# doorEntryIoT.net
KiCad netlist of a schematic drawn in EAGLE
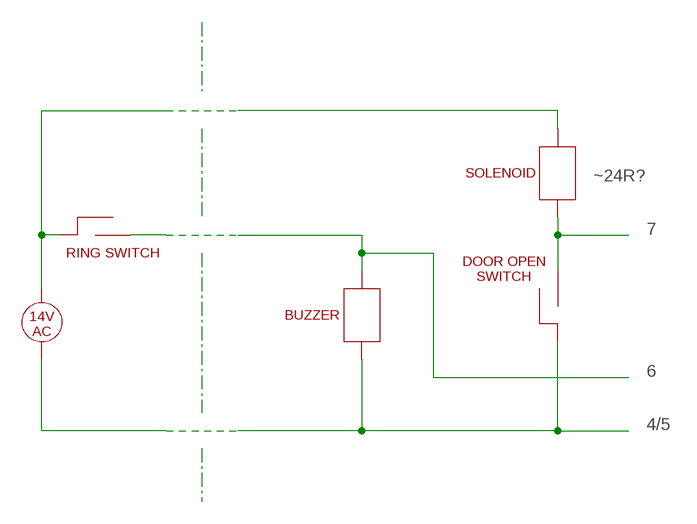
[diagram p0: schematic, sheet 1, part 1 of 2]
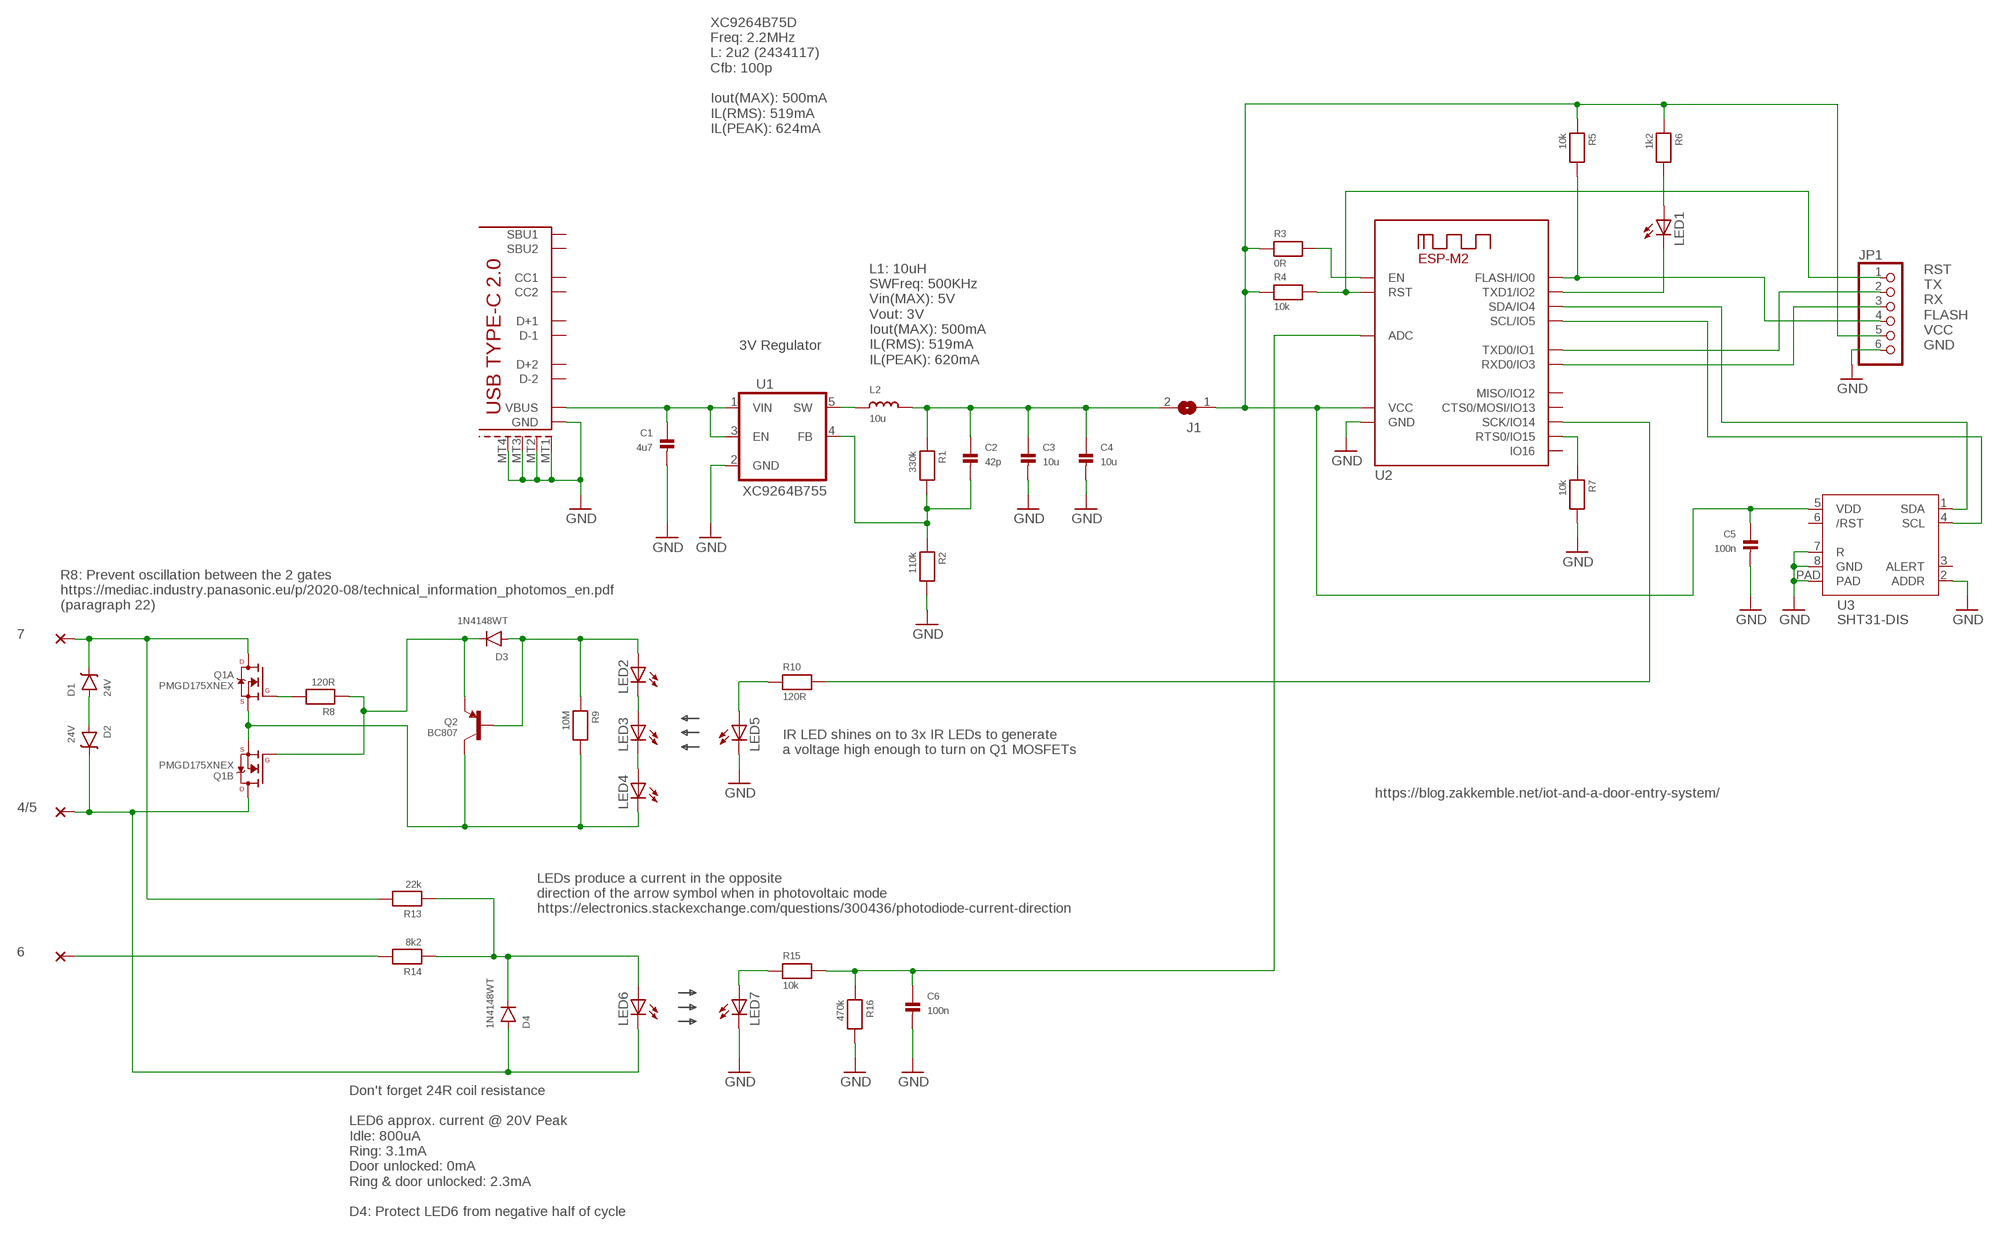
[diagram p1: schematic, sheet 1, part 2 of 2]

(export (version "E")
  (design (tool "Eeschema 10.0.6"))
  (components
    (comp (ref "C1")
      (value "4u7")
      (footprint "eagle-import:0805_NO_OUTLINE")
      (libsource (lib "eagle-import") (part "CAP_CERAMIC0805"))
    )
    (comp (ref "C2")
      (value "42p")
      (footprint "eagle-import:0402_XSMALL")
      (libsource (lib "eagle-import") (part "CAP_CERAMIC0402_XSMALL"))
    )
    (comp (ref "C3")
      (value "10u")
      (footprint "eagle-import:1206")
      (libsource (lib "eagle-import") (part "CAP_CERAMIC1206"))
    )
    (comp (ref "C4")
      (value "10u")
      (footprint "eagle-import:1206")
      (libsource (lib "eagle-import") (part "CAP_CERAMIC1206"))
    )
    (comp (ref "C5")
      (value "100n")
      (footprint "eagle-import:0402_XSMALL")
      (libsource (lib "eagle-import") (part "CAP_CERAMIC0402_XSMALL"))
    )
    (comp (ref "C6")
      (value "100n")
      (footprint "eagle-import:0402_XSMALL")
      (libsource (lib "eagle-import") (part "CAP_CERAMIC0402_XSMALL"))
    )
    (comp (ref "D1")
      (value "24V")
      (footprint "eagle-import:SMA")
      (libsource (lib "eagle-import") (part "DIODE-ZENERSMA"))
    )
    (comp (ref "D2")
      (value "24V")
      (footprint "eagle-import:SMA")
      (libsource (lib "eagle-import") (part "DIODE-ZENERSMA"))
    )
    (comp (ref "D3")
      (value "1N4148WT")
      (footprint "eagle-import:SOD-523_SM")
      (libsource (lib "eagle-import") (part "DIODESOD-523_SM"))
    )
    (comp (ref "D4")
      (value "1N4148WT")
      (footprint "eagle-import:SOD-523_SM")
      (libsource (lib "eagle-import") (part "DIODESOD-523_SM"))
    )
    (comp (ref "J1")
      (value "JUMPERSMALL")
      (footprint "eagle-import:JUMPER_SMALL")
      (libsource (lib "eagle-import") (part "JUMPERSMALL"))
    )
    (comp (ref "JP1")
      (value "PINHD-1X6")
      (footprint "eagle-import:1X06")
      (libsource (lib "eagle-import") (part "PINHD-1X6"))
    )
    (comp (ref "L2")
      (value "10u")
      (footprint "eagle-import:1210K")
      (libsource (lib "eagle-import") (part "INDUCTOR1210K"))
    )
    (comp (ref "LED1")
      (value "LED0402_XSMALL")
      (footprint "eagle-import:0402_DIODE_XSMALL")
      (libsource (lib "eagle-import") (part "LED0402_XSMALL"))
    )
    (comp (ref "LED2")
      (value "LEDSIDEVIEW")
      (footprint "eagle-import:LED_SIDEVIEW")
      (libsource (lib "eagle-import") (part "LEDSIDEVIEW"))
    )
    (comp (ref "LED3")
      (value "LEDSIDEVIEW")
      (footprint "eagle-import:LED_SIDEVIEW")
      (libsource (lib "eagle-import") (part "LEDSIDEVIEW"))
    )
    (comp (ref "LED4")
      (value "LEDSIDEVIEW")
      (footprint "eagle-import:LED_SIDEVIEW")
      (libsource (lib "eagle-import") (part "LEDSIDEVIEW"))
    )
    (comp (ref "LED5")
      (value "LEDSIDEVIEW")
      (footprint "eagle-import:LED_SIDEVIEW")
      (libsource (lib "eagle-import") (part "LEDSIDEVIEW"))
    )
    (comp (ref "LED6")
      (value "LEDSIDEVIEW")
      (footprint "eagle-import:LED_SIDEVIEW")
      (libsource (lib "eagle-import") (part "LEDSIDEVIEW"))
    )
    (comp (ref "LED7")
      (value "LEDSIDEVIEW")
      (footprint "eagle-import:LED_SIDEVIEW")
      (libsource (lib "eagle-import") (part "LEDSIDEVIEW"))
    )
    (comp (ref "PAD1")
      (value "PADSMD-1.27X2")
      (footprint "eagle-import:PAD-SMD-1.27X2")
      (libsource (lib "eagle-import") (part "PADSMD-1.27X2"))
    )
    (comp (ref "PAD2")
      (value "PADSMD-1.27X2")
      (footprint "eagle-import:PAD-SMD-1.27X2")
      (libsource (lib "eagle-import") (part "PADSMD-1.27X2"))
    )
    (comp (ref "PAD3")
      (value "PADSMD-1.27X2")
      (footprint "eagle-import:PAD-SMD-1.27X2")
      (libsource (lib "eagle-import") (part "PADSMD-1.27X2"))
    )
    (comp (ref "Q1")
      (value "PMGD175XNEX")
      (footprint "eagle-import:SOT-363")
      (fields (field (name "FARNELL") "3440057"))
      (libsource (lib "eagle-import") (part "DUAL_NMOSFETSOT-363"))
    )
    (comp (ref "Q2")
      (value "BC807")
      (footprint "eagle-import:SOT23-R")
      (libsource (lib "eagle-import") (part "TRANSISTOR_PNPSOT23-REFLOW"))
    )
    (comp (ref "R1")
      (value "330k")
      (footprint "eagle-import:0402_XSMALL")
      (libsource (lib "eagle-import") (part "RESISTOR0402_XSMALL"))
    )
    (comp (ref "R2")
      (value "110k")
      (footprint "eagle-import:0402_XSMALL")
      (libsource (lib "eagle-import") (part "RESISTOR0402_XSMALL"))
    )
    (comp (ref "R3")
      (value "0R")
      (footprint "eagle-import:0402_XSMALL")
      (libsource (lib "eagle-import") (part "RESISTOR0402_XSMALL"))
    )
    (comp (ref "R4")
      (value "10k")
      (footprint "eagle-import:0402_XSMALL")
      (libsource (lib "eagle-import") (part "RESISTOR0402_XSMALL"))
    )
    (comp (ref "R5")
      (value "10k")
      (footprint "eagle-import:0402_XSMALL")
      (libsource (lib "eagle-import") (part "RESISTOR0402_XSMALL"))
    )
    (comp (ref "R6")
      (value "1k2")
      (footprint "eagle-import:0402_XSMALL")
      (libsource (lib "eagle-import") (part "RESISTOR0402_XSMALL"))
    )
    (comp (ref "R7")
      (value "10k")
      (footprint "eagle-import:0402_XSMALL")
      (libsource (lib "eagle-import") (part "RESISTOR0402_XSMALL"))
    )
    (comp (ref "R8")
      (value "120R")
      (footprint "eagle-import:0402_XSMALL")
      (libsource (lib "eagle-import") (part "RESISTOR0402_XSMALL"))
    )
    (comp (ref "R9")
      (value "10M")
      (footprint "eagle-import:0402_XSMALL")
      (libsource (lib "eagle-import") (part "RESISTOR0402_XSMALL"))
    )
    (comp (ref "R10")
      (value "120R")
      (footprint "eagle-import:0402_XSMALL")
      (libsource (lib "eagle-import") (part "RESISTOR0402_XSMALL"))
    )
    (comp (ref "R13")
      (value "22k")
      (footprint "eagle-import:0402_XSMALL")
      (libsource (lib "eagle-import") (part "RESISTOR0402_XSMALL"))
    )
    (comp (ref "R14")
      (value "8k2")
      (footprint "eagle-import:1206")
      (libsource (lib "eagle-import") (part "RESISTOR1206"))
    )
    (comp (ref "R15")
      (value "10k")
      (footprint "eagle-import:0402_XSMALL")
      (libsource (lib "eagle-import") (part "RESISTOR0402_XSMALL"))
    )
    (comp (ref "R16")
      (value "470k")
      (footprint "eagle-import:0402_XSMALL")
      (libsource (lib "eagle-import") (part "RESISTOR0402_XSMALL"))
    )
    (comp (ref "U1")
      (value "XC9264B755")
      (footprint "eagle-import:SOT23-5_SM_PAD")
      (libsource (lib "eagle-import") (part "SWITCH_REGCONFIG2"))
    )
    (comp (ref "U2")
      (value "ESP-M2")
      (footprint "eagle-import:ESP-M2")
      (libsource (lib "eagle-import") (part "ESP-M2"))
    )
    (comp (ref "U3")
      (value "SHT31-DIS")
      (footprint "eagle-import:DFN_2.5X2.5_8")
      (libsource (lib "eagle-import") (part "SHT3X-DIS"))
    )
    (comp (ref "USB1")
      (value "USB-TYPE-C-2.0SMD")
      (footprint "eagle-import:USB-C-2.0_SMD")
      (libsource (lib "eagle-import") (part "USB-TYPE-C-2.0SMD"))
    )
  )
  (nets
    (net (code "1") (name "GND") (class "Default")
      (node (ref "C1") (pin "2") (pinfunction "P$2_2") (pintype "passive"))
      (node (ref "C3") (pin "2") (pinfunction "P$2_2") (pintype "passive"))
      (node (ref "C4") (pin "2") (pinfunction "P$2_2") (pintype "passive"))
      (node (ref "C5") (pin "2") (pinfunction "P$2_2") (pintype "passive"))
      (node (ref "C6") (pin "2") (pinfunction "P$2_2") (pintype "passive"))
      (node (ref "JP1") (pin "6") (pinfunction "6_6") (pintype "passive"))
      (node (ref "LED5") (pin "1") (pinfunction "C_1") (pintype "passive"))
      (node (ref "LED7") (pin "1") (pinfunction "C_1") (pintype "passive"))
      (node (ref "R16") (pin "2") (pinfunction "2_2") (pintype "passive"))
      (node (ref "R2") (pin "2") (pinfunction "2_2") (pintype "passive"))
      (node (ref "R7") (pin "2") (pinfunction "2_2") (pintype "passive"))
      (node (ref "U1") (pin "2") (pinfunction "GND_2") (pintype "passive"))
      (node (ref "U2") (pin "8") (pinfunction "GND_8") (pintype "bidirectional"))
      (node (ref "U3") (pin "2") (pinfunction "ADDR_2") (pintype "bidirectional"))
      (node (ref "U3") (pin "7") (pinfunction "R_7") (pintype "bidirectional"))
      (node (ref "U3") (pin "8") (pinfunction "GND_8") (pintype "bidirectional"))
      (node (ref "U3") (pin "PAD") (pinfunction "PAD_PAD") (pintype "bidirectional"))
      (node (ref "USB1") (pin "A12B1") (pinfunction "GND_A12B1") (pintype "bidirectional"))
      (node (ref "USB1") (pin "A1B2") (pinfunction "GND_A1B2") (pintype "bidirectional"))
      (node (ref "USB1") (pin "MT1") (pinfunction "SHEILD1_MT1") (pintype "bidirectional"))
      (node (ref "USB1") (pin "MT2") (pinfunction "SHEILD2_MT2") (pintype "bidirectional"))
      (node (ref "USB1") (pin "MT3") (pinfunction "SHEILD3_MT3") (pintype "bidirectional"))
      (node (ref "USB1") (pin "MT4") (pinfunction "SHEILD4_MT4") (pintype "bidirectional"))
    )
    (net (code "2") (name "Net-(C1-P$1)") (class "Default")
      (node (ref "C1") (pin "1") (pinfunction "P$1_1") (pintype "passive"))
      (node (ref "U1") (pin "1") (pinfunction "VIN_1") (pintype "power_in"))
      (node (ref "U1") (pin "3") (pinfunction "EN_3") (pintype "input"))
      (node (ref "USB1") (pin "A4B9") (pinfunction "VBUS_A4B9") (pintype "bidirectional"))
      (node (ref "USB1") (pin "A9B4") (pinfunction "VBUS_A9B4") (pintype "bidirectional"))
    )
    (net (code "3") (name "Net-(C2-P$1)") (class "Default")
      (node (ref "C2") (pin "1") (pinfunction "P$1_1") (pintype "passive"))
      (node (ref "C3") (pin "1") (pinfunction "P$1_1") (pintype "passive"))
      (node (ref "C4") (pin "1") (pinfunction "P$1_1") (pintype "passive"))
      (node (ref "J1") (pin "2") (pinfunction "2_2") (pintype "passive"))
      (node (ref "L2") (pin "2") (pinfunction "2_2") (pintype "passive"))
      (node (ref "R1") (pin "1") (pinfunction "1_1") (pintype "passive"))
    )
    (net (code "4") (name "Net-(C2-P$2)") (class "Default")
      (node (ref "C2") (pin "2") (pinfunction "P$2_2") (pintype "passive"))
      (node (ref "R1") (pin "2") (pinfunction "2_2") (pintype "passive"))
      (node (ref "R2") (pin "1") (pinfunction "1_1") (pintype "passive"))
      (node (ref "U1") (pin "4") (pinfunction "FB_4") (pintype "input"))
    )
    (net (code "5") (name "Net-(C5-P$1)") (class "Default")
      (node (ref "C5") (pin "1") (pinfunction "P$1_1") (pintype "passive"))
      (node (ref "J1") (pin "1") (pinfunction "1_1") (pintype "passive"))
      (node (ref "JP1") (pin "5") (pinfunction "5_5") (pintype "passive"))
      (node (ref "R3") (pin "1") (pinfunction "1_1") (pintype "passive"))
      (node (ref "R4") (pin "1") (pinfunction "1_1") (pintype "passive"))
      (node (ref "R5") (pin "1") (pinfunction "1_1") (pintype "passive"))
      (node (ref "R6") (pin "1") (pinfunction "1_1") (pintype "passive"))
      (node (ref "U2") (pin "7") (pinfunction "VCC_7") (pintype "bidirectional"))
      (node (ref "U3") (pin "5") (pinfunction "VDD_5") (pintype "bidirectional"))
    )
    (net (code "6") (name "Net-(C6-P$1)") (class "Default")
      (node (ref "C6") (pin "1") (pinfunction "P$1_1") (pintype "passive"))
      (node (ref "R15") (pin "2") (pinfunction "2_2") (pintype "passive"))
      (node (ref "R16") (pin "1") (pinfunction "1_1") (pintype "passive"))
      (node (ref "U2") (pin "1") (pinfunction "ADC_1") (pintype "bidirectional"))
    )
    (net (code "7") (name "Net-(D1-PadA)") (class "Default")
      (node (ref "D1") (pin "A") (pinfunction "A_A") (pintype "passive"))
      (node (ref "D2") (pin "A") (pinfunction "A_A") (pintype "passive"))
    )
    (net (code "8") (name "Net-(D3-C)") (class "Default")
      (node (ref "D3") (pin "K") (pinfunction "C_K") (pintype "passive"))
      (node (ref "Q1") (pin "5") (pinfunction "G_5") (pintype "passive"))
      (node (ref "Q2") (pin "2") (pinfunction "E_2") (pintype "passive"))
      (node (ref "R8") (pin "1") (pinfunction "1_1") (pintype "passive"))
    )
    (net (code "9") (name "Net-(D4-C)") (class "Default")
      (node (ref "D4") (pin "K") (pinfunction "C_K") (pintype "passive"))
      (node (ref "LED6") (pin "2") (pinfunction "A_2") (pintype "passive"))
      (node (ref "R13") (pin "1") (pinfunction "1_1") (pintype "passive"))
      (node (ref "R14") (pin "1") (pinfunction "1_1") (pintype "passive"))
    )
    (net (code "10") (name "Net-(LED1-A)") (class "Default")
      (node (ref "LED1") (pin "1") (pinfunction "A_1") (pintype "passive"))
      (node (ref "R6") (pin "2") (pinfunction "2_2") (pintype "passive"))
    )
    (net (code "11") (name "Net-(LED1-C)") (class "Default")
      (node (ref "LED1") (pin "2") (pinfunction "C_2") (pintype "passive"))
      (node (ref "U2") (pin "9") (pinfunction "TXD1/IO2_9") (pintype "bidirectional"))
    )
    (net (code "12") (name "Net-(LED2-A)") (class "Default")
      (node (ref "D3") (pin "A") (pinfunction "A_A") (pintype "passive"))
      (node (ref "LED2") (pin "2") (pinfunction "A_2") (pintype "passive"))
      (node (ref "Q2") (pin "1") (pinfunction "B_1") (pintype "passive"))
      (node (ref "R9") (pin "1") (pinfunction "1_1") (pintype "passive"))
    )
    (net (code "13") (name "Net-(LED2-C)") (class "Default")
      (node (ref "LED2") (pin "1") (pinfunction "C_1") (pintype "passive"))
      (node (ref "LED3") (pin "2") (pinfunction "A_2") (pintype "passive"))
    )
    (net (code "14") (name "Net-(LED3-C)") (class "Default")
      (node (ref "LED3") (pin "1") (pinfunction "C_1") (pintype "passive"))
      (node (ref "LED4") (pin "2") (pinfunction "A_2") (pintype "passive"))
    )
    (net (code "15") (name "Net-(LED4-C)") (class "Default")
      (node (ref "LED4") (pin "1") (pinfunction "C_1") (pintype "passive"))
      (node (ref "Q1") (pin "1") (pinfunction "S_1") (pintype "passive"))
      (node (ref "Q1") (pin "4") (pinfunction "S_4") (pintype "passive"))
      (node (ref "Q2") (pin "3") (pinfunction "C_3") (pintype "passive"))
      (node (ref "R9") (pin "2") (pinfunction "2_2") (pintype "passive"))
    )
    (net (code "16") (name "Net-(LED5-A)") (class "Default")
      (node (ref "LED5") (pin "2") (pinfunction "A_2") (pintype "passive"))
      (node (ref "R10") (pin "1") (pinfunction "1_1") (pintype "passive"))
    )
    (net (code "17") (name "Net-(LED6-C)") (class "Default")
      (node (ref "D2") (pin "C") (pinfunction "C_C") (pintype "passive"))
      (node (ref "D4") (pin "A") (pinfunction "A_A") (pintype "passive"))
      (node (ref "LED6") (pin "1") (pinfunction "C_1") (pintype "passive"))
      (node (ref "PAD2") (pin "1") (pinfunction "P$1_1") (pintype "passive"))
      (node (ref "Q1") (pin "3") (pinfunction "D_3") (pintype "passive"))
    )
    (net (code "18") (name "Net-(LED7-A)") (class "Default")
      (node (ref "LED7") (pin "2") (pinfunction "A_2") (pintype "passive"))
      (node (ref "R15") (pin "1") (pinfunction "1_1") (pintype "passive"))
    )
    (net (code "19") (name "Net-(PAD1-P$1)") (class "Default")
      (node (ref "PAD1") (pin "1") (pinfunction "P$1_1") (pintype "passive"))
      (node (ref "R14") (pin "2") (pinfunction "2_2") (pintype "passive"))
    )
    (net (code "20") (name "Net-(PAD3-P$1)") (class "Default")
      (node (ref "D1") (pin "C") (pinfunction "C_C") (pintype "passive"))
      (node (ref "PAD3") (pin "1") (pinfunction "P$1_1") (pintype "passive"))
      (node (ref "Q1") (pin "6") (pinfunction "D_6") (pintype "passive"))
      (node (ref "R13") (pin "2") (pinfunction "2_2") (pintype "passive"))
    )
    (net (code "21") (name "Net-(Q1A-G)") (class "Default")
      (node (ref "Q1") (pin "2") (pinfunction "G_2") (pintype "passive"))
      (node (ref "R8") (pin "2") (pinfunction "2_2") (pintype "passive"))
    )
    (net (code "22") (name "Net-(U1-SW)") (class "Default")
      (node (ref "L2") (pin "1") (pinfunction "1_1") (pintype "passive"))
      (node (ref "U1") (pin "5") (pinfunction "SW_5") (pintype "output"))
    )
    (net (code "23") (name "Net-(U2-EN)") (class "Default")
      (node (ref "R3") (pin "2") (pinfunction "2_2") (pintype "passive"))
      (node (ref "U2") (pin "2") (pinfunction "EN_2") (pintype "bidirectional"))
    )
    (net (code "24") (name "Net-(U2-FLASH{slash}IO0)") (class "Default")
      (node (ref "JP1") (pin "4") (pinfunction "4_4") (pintype "passive"))
      (node (ref "R5") (pin "2") (pinfunction "2_2") (pintype "passive"))
      (node (ref "U2") (pin "10") (pinfunction "FLASH/IO0_10") (pintype "bidirectional"))
    )
    (net (code "25") (name "Net-(U2-RST)") (class "Default")
      (node (ref "JP1") (pin "1") (pinfunction "1_1") (pintype "passive"))
      (node (ref "R4") (pin "2") (pinfunction "2_2") (pintype "passive"))
      (node (ref "U2") (pin "15") (pinfunction "RST_15") (pintype "bidirectional"))
    )
    (net (code "26") (name "Net-(U2-RTS0{slash}IO15)") (class "Default")
      (node (ref "R7") (pin "1") (pinfunction "1_1") (pintype "passive"))
      (node (ref "U2") (pin "6") (pinfunction "RTS0/IO15_6") (pintype "bidirectional"))
    )
    (net (code "27") (name "Net-(U2-RXD0{slash}IO3)") (class "Default")
      (node (ref "JP1") (pin "3") (pinfunction "3_3") (pintype "passive"))
      (node (ref "U2") (pin "13") (pinfunction "RXD0/IO3_13") (pintype "bidirectional"))
    )
    (net (code "28") (name "Net-(U2-SCK{slash}IO14)") (class "Default")
      (node (ref "R10") (pin "2") (pinfunction "2_2") (pintype "passive"))
      (node (ref "U2") (pin "3") (pinfunction "SCK/IO14_3") (pintype "bidirectional"))
    )
    (net (code "29") (name "Net-(U2-SCL{slash}IO5)") (class "Default")
      (node (ref "U2") (pin "12") (pinfunction "SCL/IO5_12") (pintype "bidirectional"))
      (node (ref "U3") (pin "4") (pinfunction "SCL_4") (pintype "bidirectional"))
    )
    (net (code "30") (name "Net-(U2-SDA{slash}IO4)") (class "Default")
      (node (ref "U2") (pin "11") (pinfunction "SDA/IO4_11") (pintype "bidirectional"))
      (node (ref "U3") (pin "1") (pinfunction "SDA_1") (pintype "bidirectional"))
    )
    (net (code "31") (name "Net-(U2-TXD0{slash}IO1)") (class "Default")
      (node (ref "JP1") (pin "2") (pinfunction "2_2") (pintype "passive"))
      (node (ref "U2") (pin "14") (pinfunction "TXD0/IO1_14") (pintype "bidirectional"))
    )
    (net (code "32") (name "unconnected-(U2-CTS0{slash}MOSI{slash}IO13-Pad5)") (class "Default")
      (node (ref "U2") (pin "5") (pinfunction "CTS0/MOSI/IO13_5") (pintype "bidirectional"))
    )
    (net (code "33") (name "unconnected-(U2-IO16-Pad16)") (class "Default")
      (node (ref "U2") (pin "16") (pinfunction "IO16_16") (pintype "bidirectional"))
    )
    (net (code "34") (name "unconnected-(U2-MISO{slash}IO12-Pad4)") (class "Default")
      (node (ref "U2") (pin "4") (pinfunction "MISO/IO12_4") (pintype "bidirectional"))
    )
    (net (code "35") (name "unconnected-(U3-ALERT-Pad3)") (class "Default")
      (node (ref "U3") (pin "3") (pinfunction "ALERT_3") (pintype "bidirectional"))
    )
    (net (code "36") (name "unconnected-(U3-{slash}RST-Pad6)") (class "Default")
      (node (ref "U3") (pin "6") (pinfunction "/RST_6") (pintype "bidirectional"))
    )
    (net (code "37") (name "unconnected-(USB1-CC1-PadA5)") (class "Default")
      (node (ref "USB1") (pin "A5") (pinfunction "CC1_A5") (pintype "bidirectional"))
    )
    (net (code "38") (name "unconnected-(USB1-CC2-PadB5)") (class "Default")
      (node (ref "USB1") (pin "B5") (pinfunction "CC2_B5") (pintype "bidirectional"))
    )
    (net (code "39") (name "unconnected-(USB1-D+1-PadA6)") (class "Default")
      (node (ref "USB1") (pin "A6") (pinfunction "D+1_A6") (pintype "bidirectional"))
    )
    (net (code "40") (name "unconnected-(USB1-D+2-PadB6)") (class "Default")
      (node (ref "USB1") (pin "B6") (pinfunction "D+2_B6") (pintype "bidirectional"))
    )
    (net (code "41") (name "unconnected-(USB1-D-1-PadA7)") (class "Default")
      (node (ref "USB1") (pin "A7") (pinfunction "D-1_A7") (pintype "bidirectional"))
    )
    (net (code "42") (name "unconnected-(USB1-D-2-PadB7)") (class "Default")
      (node (ref "USB1") (pin "B7") (pinfunction "D-2_B7") (pintype "bidirectional"))
    )
    (net (code "43") (name "unconnected-(USB1-SBU1-PadA8)") (class "Default")
      (node (ref "USB1") (pin "A8") (pinfunction "SBU1_A8") (pintype "bidirectional"))
    )
    (net (code "44") (name "unconnected-(USB1-SBU2-PadB8)") (class "Default")
      (node (ref "USB1") (pin "B8") (pinfunction "SBU2_B8") (pintype "bidirectional"))
    )
  )
)
